# version3_PNP.net
KiCad netlist of a schematic drawn in EAGLE
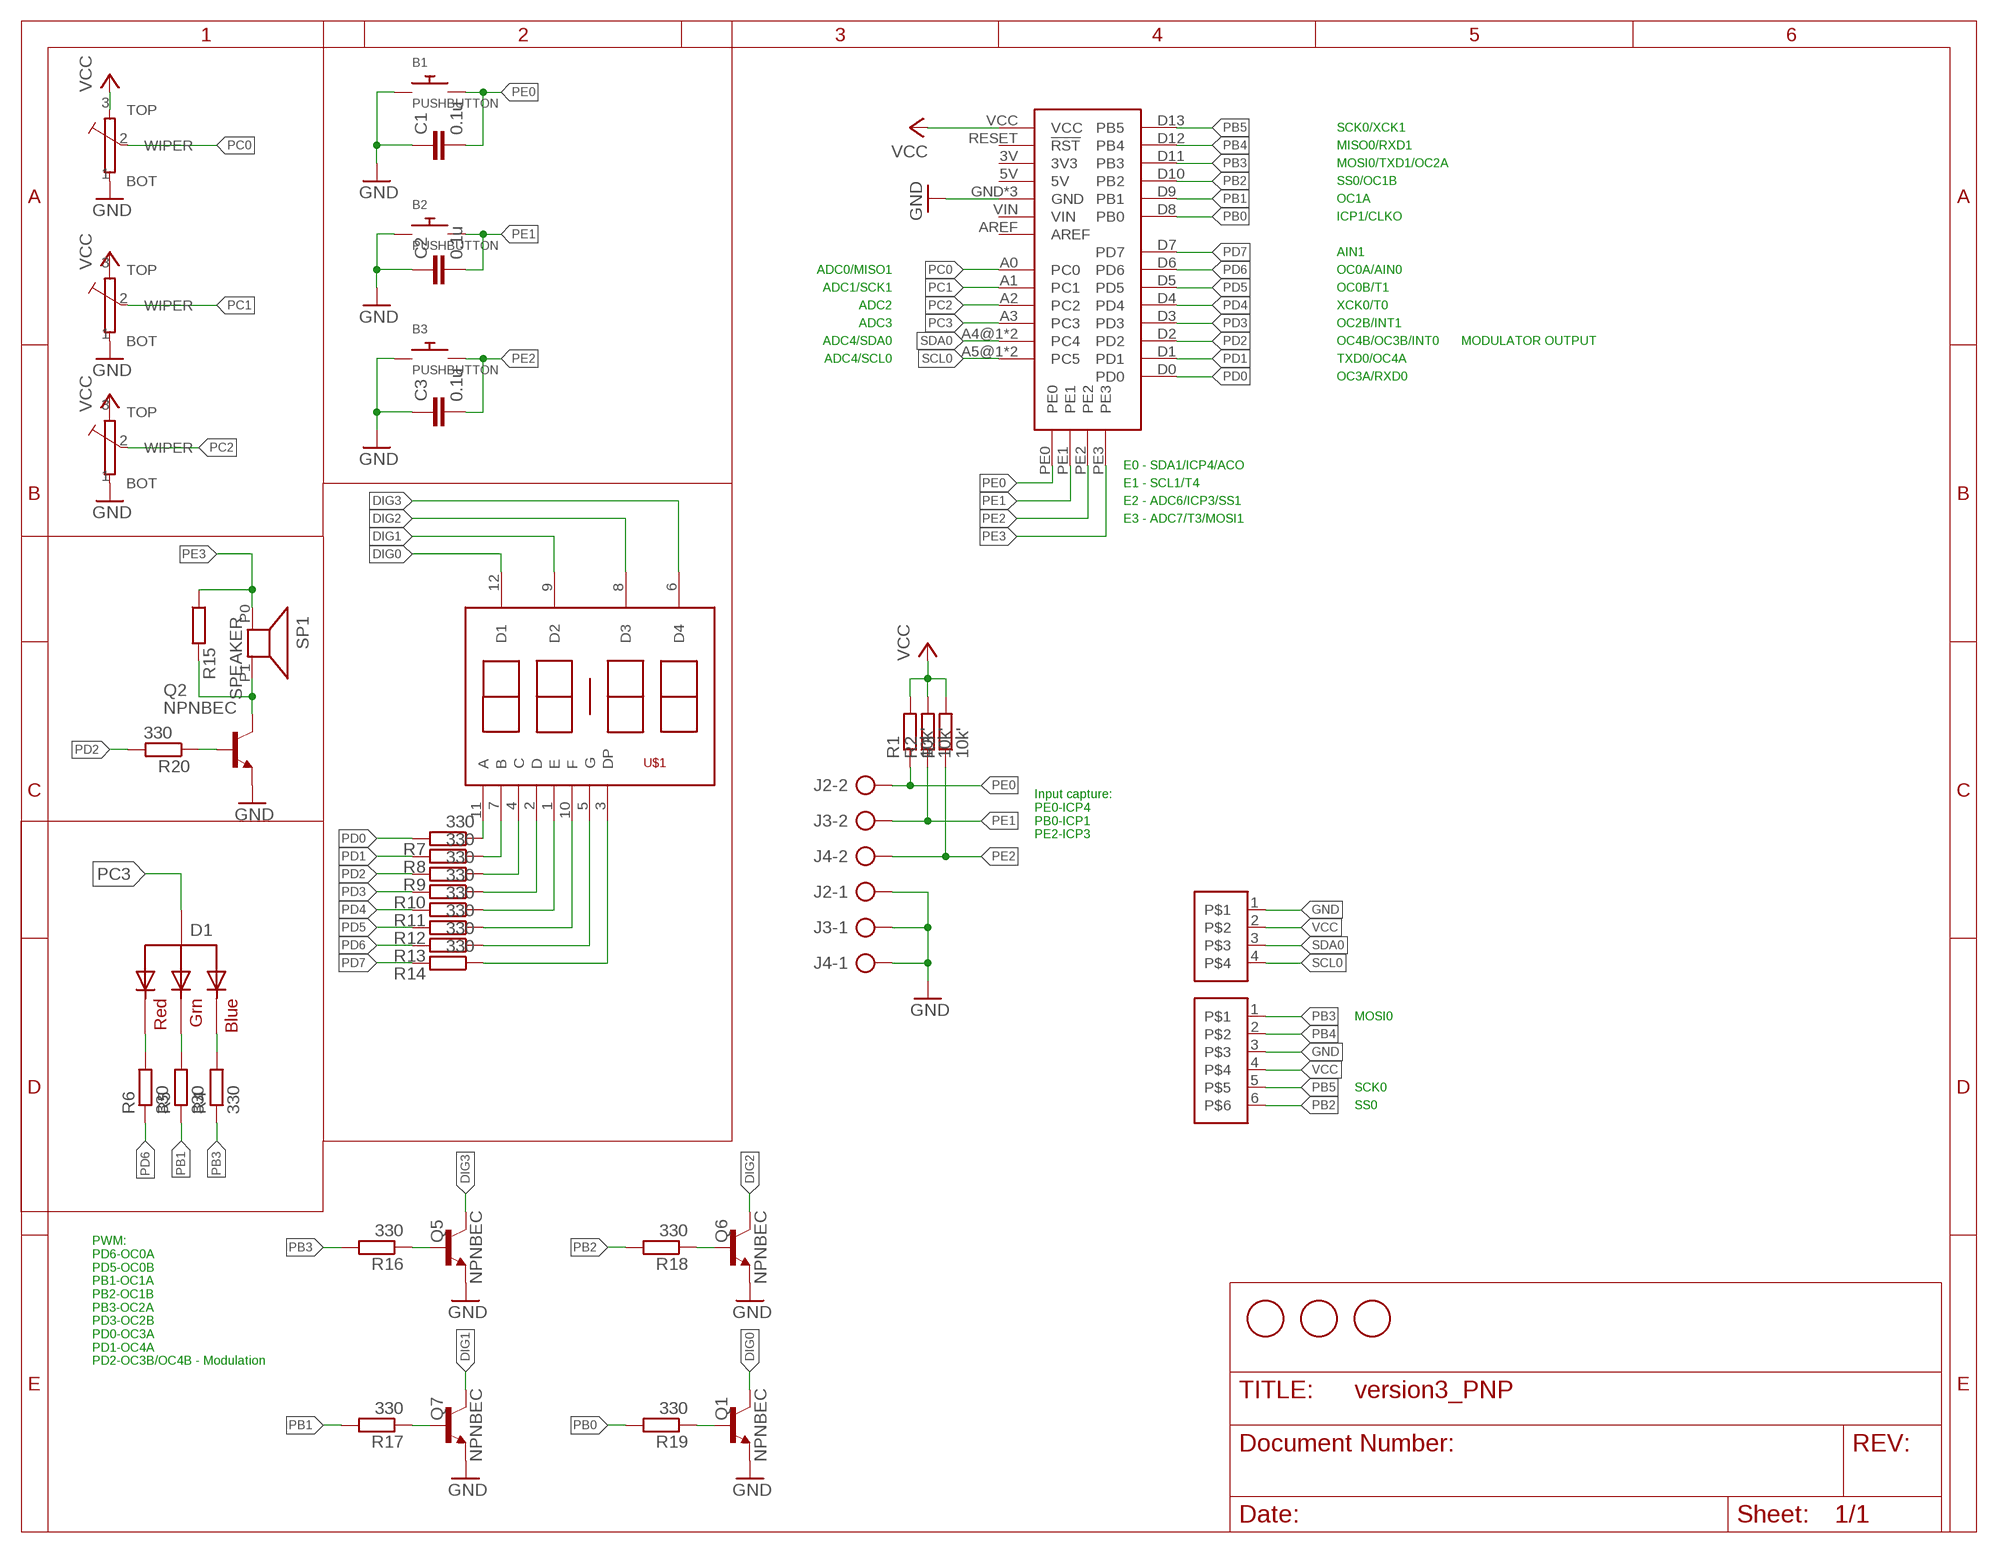
[diagram p0: schematic, sheet 1]

(export (version "E")
  (design (tool "Eeschema 10.0.6"))
  (components
    (comp (ref "AFID1")
      (value "FIDUCIAL")
      (footprint "eagle-import:FIDUCIAL_1MM")
      (libsource (lib "eagle-import") (part "FIDUCIAL"))
    )
    (comp (ref "AFID2")
      (value "FIDUCIAL")
      (footprint "eagle-import:FIDUCIAL_1MM")
      (libsource (lib "eagle-import") (part "FIDUCIAL"))
    )
    (comp (ref "AFID3")
      (value "FIDUCIAL")
      (footprint "eagle-import:FIDUCIAL_1MM")
      (libsource (lib "eagle-import") (part "FIDUCIAL"))
    )
    (comp (ref "B1")
      (value "PUSHBUTTON")
      (footprint "eagle-import:BUTTON_EVPBF")
      (libsource (lib "eagle-import") (part "PUSHBUTTON"))
    )
    (comp (ref "B2")
      (value "PUSHBUTTON")
      (footprint "eagle-import:BUTTON_EVPBF")
      (libsource (lib "eagle-import") (part "PUSHBUTTON"))
    )
    (comp (ref "B3")
      (value "PUSHBUTTON")
      (footprint "eagle-import:BUTTON_EVPBF")
      (libsource (lib "eagle-import") (part "PUSHBUTTON"))
    )
    (comp (ref "C1")
      (value "0.1u")
      (footprint "eagle-import:C0805")
      (libsource (lib "eagle-import") (part "C-EUC0805"))
    )
    (comp (ref "C2")
      (value "0.1u")
      (footprint "eagle-import:C0805")
      (libsource (lib "eagle-import") (part "C-EUC0805"))
    )
    (comp (ref "C3")
      (value "0.1u")
      (footprint "eagle-import:C0805")
      (libsource (lib "eagle-import") (part "C-EUC0805"))
    )
    (comp (ref "D1")
      (value "RGB_CA")
      (footprint "eagle-import:PLCC-4")
      (libsource (lib "eagle-import") (part "RGB_CA"))
    )
    (comp (ref "J1")
      (value "M04F")
      (footprint "eagle-import:1X04_FEMALE")
      (libsource (lib "eagle-import") (part "M04F"))
    )
    (comp (ref "J2")
      (value "1X02CLEAN")
      (footprint "eagle-import:1X02_CLEAN")
      (libsource (lib "eagle-import") (part "1X02CLEAN"))
    )
    (comp (ref "J3")
      (value "1X02CLEAN")
      (footprint "eagle-import:1X02_CLEAN")
      (libsource (lib "eagle-import") (part "1X02CLEAN"))
    )
    (comp (ref "J4")
      (value "1X02CLEAN")
      (footprint "eagle-import:1X02_CLEAN")
      (libsource (lib "eagle-import") (part "1X02CLEAN"))
    )
    (comp (ref "Q1")
      (value "NPNBEC")
      (footprint "eagle-import:SOT23")
      (libsource (lib "eagle-import") (part "NPNBEC"))
    )
    (comp (ref "Q2")
      (value "NPNBEC")
      (footprint "eagle-import:SOT23")
      (libsource (lib "eagle-import") (part "NPNBEC"))
    )
    (comp (ref "Q5")
      (value "NPNBEC")
      (footprint "eagle-import:SOT23")
      (libsource (lib "eagle-import") (part "NPNBEC"))
    )
    (comp (ref "Q6")
      (value "NPNBEC")
      (footprint "eagle-import:SOT23")
      (libsource (lib "eagle-import") (part "NPNBEC"))
    )
    (comp (ref "Q7")
      (value "NPNBEC")
      (footprint "eagle-import:SOT23")
      (libsource (lib "eagle-import") (part "NPNBEC"))
    )
    (comp (ref "R1")
      (value "10k'")
      (footprint "eagle-import:R0805")
      (libsource (lib "eagle-import") (part "R-EU_R0805"))
    )
    (comp (ref "R2")
      (value "10k'")
      (footprint "eagle-import:R0805")
      (libsource (lib "eagle-import") (part "R-EU_R0805"))
    )
    (comp (ref "R3")
      (value "10k'")
      (footprint "eagle-import:R0805")
      (libsource (lib "eagle-import") (part "R-EU_R0805"))
    )
    (comp (ref "R4")
      (value "330")
      (footprint "eagle-import:R0805")
      (libsource (lib "eagle-import") (part "R-EU_R0805"))
    )
    (comp (ref "R5")
      (value "330")
      (footprint "eagle-import:R0805")
      (libsource (lib "eagle-import") (part "R-EU_R0805"))
    )
    (comp (ref "R6")
      (value "330")
      (footprint "eagle-import:R0805")
      (libsource (lib "eagle-import") (part "R-EU_R0805"))
    )
    (comp (ref "R7")
      (value "330")
      (footprint "eagle-import:R0805")
      (libsource (lib "eagle-import") (part "R-EU_R0805"))
    )
    (comp (ref "R8")
      (value "330")
      (footprint "eagle-import:R0805")
      (libsource (lib "eagle-import") (part "R-EU_R0805"))
    )
    (comp (ref "R9")
      (value "330")
      (footprint "eagle-import:R0805")
      (libsource (lib "eagle-import") (part "R-EU_R0805"))
    )
    (comp (ref "R10")
      (value "330")
      (footprint "eagle-import:R0805")
      (libsource (lib "eagle-import") (part "R-EU_R0805"))
    )
    (comp (ref "R11")
      (value "330")
      (footprint "eagle-import:R0805")
      (libsource (lib "eagle-import") (part "R-EU_R0805"))
    )
    (comp (ref "R12")
      (value "330")
      (footprint "eagle-import:R0805")
      (libsource (lib "eagle-import") (part "R-EU_R0805"))
    )
    (comp (ref "R13")
      (value "330")
      (footprint "eagle-import:R0805")
      (libsource (lib "eagle-import") (part "R-EU_R0805"))
    )
    (comp (ref "R14")
      (value "330")
      (footprint "eagle-import:R0805")
      (libsource (lib "eagle-import") (part "R-EU_R0805"))
    )
    (comp (ref "R15")
      (value "R-EU_R0805")
      (footprint "eagle-import:R0805")
      (libsource (lib "eagle-import") (part "R-EU_R0805"))
    )
    (comp (ref "R16")
      (value "330")
      (footprint "eagle-import:R0805")
      (libsource (lib "eagle-import") (part "R-EU_R0805"))
    )
    (comp (ref "R17")
      (value "330")
      (footprint "eagle-import:R0805")
      (libsource (lib "eagle-import") (part "R-EU_R0805"))
    )
    (comp (ref "R18")
      (value "330")
      (footprint "eagle-import:R0805")
      (libsource (lib "eagle-import") (part "R-EU_R0805"))
    )
    (comp (ref "R19")
      (value "330")
      (footprint "eagle-import:R0805")
      (libsource (lib "eagle-import") (part "R-EU_R0805"))
    )
    (comp (ref "R20")
      (value "330")
      (footprint "eagle-import:R0805")
      (libsource (lib "eagle-import") (part "R-EU_R0805"))
    )
    (comp (ref "SP1")
      (value "SPEAKER")
      (footprint "eagle-import:PKMCS_SPEAKER")
      (libsource (lib "eagle-import") (part "SPEAKER"))
    )
    (comp (ref "TR1")
      (value "TRIMMTHUMB")
      (footprint "eagle-import:RV09")
      (libsource (lib "eagle-import") (part "TRIMMTHUMB"))
    )
    (comp (ref "TR2")
      (value "TRIMMTHUMB")
      (footprint "eagle-import:RV09")
      (libsource (lib "eagle-import") (part "TRIMMTHUMB"))
    )
    (comp (ref "TR3")
      (value "TRIMMTHUMB")
      (footprint "eagle-import:RV09")
      (libsource (lib "eagle-import") (part "TRIMMTHUMB"))
    )
    (comp (ref "U$1")
      (value "4DIG_7SEG_CATHODE")
      (footprint "eagle-import:4DIG_7SEG_CLOCK")
      (libsource (lib "eagle-import") (part "4DIG_7SEG_CATHODE"))
    )
    (comp (ref "U$2")
      (value "M06F")
      (footprint "eagle-import:1X06_FEMALE")
      (libsource (lib "eagle-import") (part "M06F"))
    )
    (comp (ref "U2")
      (value "XPLAINEDMINI328PB")
      (footprint "eagle-import:XPLAINEDMINI328P")
      (libsource (lib "eagle-import") (part "XPLAINEDMINI328PB"))
    )
  )
  (nets
    (net (code "1") (name "DIG0") (class "Default")
      (node (ref "Q1") (pin "3") (pinfunction "C_3") (pintype "passive"))
      (node (ref "U$1") (pin "12") (pinfunction "D1_12") (pintype "bidirectional"))
    )
    (net (code "2") (name "DIG1") (class "Default")
      (node (ref "Q7") (pin "3") (pinfunction "C_3") (pintype "passive"))
      (node (ref "U$1") (pin "9") (pinfunction "D2_9") (pintype "bidirectional"))
    )
    (net (code "3") (name "DIG2") (class "Default")
      (node (ref "Q6") (pin "3") (pinfunction "C_3") (pintype "passive"))
      (node (ref "U$1") (pin "8") (pinfunction "D3_8") (pintype "bidirectional"))
    )
    (net (code "4") (name "DIG3") (class "Default")
      (node (ref "Q5") (pin "3") (pinfunction "C_3") (pintype "passive"))
      (node (ref "U$1") (pin "6") (pinfunction "D4_6") (pintype "bidirectional"))
    )
    (net (code "5") (name "GND") (class "Default")
      (node (ref "B1") (pin "A1") (pinfunction "P$1_A1") (pintype "passive"))
      (node (ref "B1") (pin "A2") (pinfunction "P$1_A2") (pintype "passive"))
      (node (ref "B2") (pin "A1") (pinfunction "P$1_A1") (pintype "passive"))
      (node (ref "B2") (pin "A2") (pinfunction "P$1_A2") (pintype "passive"))
      (node (ref "B3") (pin "A1") (pinfunction "P$1_A1") (pintype "passive"))
      (node (ref "B3") (pin "A2") (pinfunction "P$1_A2") (pintype "passive"))
      (node (ref "C1") (pin "1") (pinfunction "1_1") (pintype "passive"))
      (node (ref "C2") (pin "1") (pinfunction "1_1") (pintype "passive"))
      (node (ref "C3") (pin "1") (pinfunction "1_1") (pintype "passive"))
      (node (ref "J1") (pin "1") (pinfunction "P$1_1") (pintype "bidirectional"))
      (node (ref "J2") (pin "1") (pinfunction "KL_1") (pintype "passive"))
      (node (ref "J3") (pin "1") (pinfunction "KL_1") (pintype "passive"))
      (node (ref "J4") (pin "1") (pinfunction "KL_1") (pintype "passive"))
      (node (ref "Q1") (pin "2") (pinfunction "E_2") (pintype "passive"))
      (node (ref "Q2") (pin "2") (pinfunction "E_2") (pintype "passive"))
      (node (ref "Q5") (pin "2") (pinfunction "E_2") (pintype "passive"))
      (node (ref "Q6") (pin "2") (pinfunction "E_2") (pintype "passive"))
      (node (ref "Q7") (pin "2") (pinfunction "E_2") (pintype "passive"))
      (node (ref "TR1") (pin "1") (pinfunction "BOT_1") (pintype "bidirectional"))
      (node (ref "TR2") (pin "1") (pinfunction "BOT_1") (pintype "bidirectional"))
      (node (ref "TR3") (pin "1") (pinfunction "BOT_1") (pintype "bidirectional"))
      (node (ref "U$2") (pin "3") (pinfunction "P$3_3") (pintype "bidirectional"))
      (node (ref "U2") (pin "GND") (pinfunction "GND_GND") (pintype "bidirectional"))
      (node (ref "U2") (pin "GND1") (pinfunction "GND_GND1") (pintype "bidirectional"))
      (node (ref "U2") (pin "GND2") (pinfunction "GND_GND2") (pintype "bidirectional"))
    )
    (net (code "6") (name "Net-(D1-BLUE)") (class "Default")
      (node (ref "D1") (pin "P2") (pinfunction "BLUE_P2") (pintype "bidirectional"))
      (node (ref "R4") (pin "2") (pinfunction "2_2") (pintype "passive"))
    )
    (net (code "7") (name "Net-(D1-GREEN)") (class "Default")
      (node (ref "D1") (pin "P3") (pinfunction "GREEN_P3") (pintype "bidirectional"))
      (node (ref "R5") (pin "2") (pinfunction "2_2") (pintype "passive"))
    )
    (net (code "8") (name "Net-(D1-RED)") (class "Default")
      (node (ref "D1") (pin "P4") (pinfunction "RED_P4") (pintype "bidirectional"))
      (node (ref "R6") (pin "2") (pinfunction "2_2") (pintype "passive"))
    )
    (net (code "9") (name "Net-(Q1-B)") (class "Default")
      (node (ref "Q1") (pin "1") (pinfunction "B_1") (pintype "passive"))
      (node (ref "R19") (pin "1") (pinfunction "1_1") (pintype "passive"))
    )
    (net (code "10") (name "Net-(Q2-B)") (class "Default")
      (node (ref "Q2") (pin "1") (pinfunction "B_1") (pintype "passive"))
      (node (ref "R20") (pin "1") (pinfunction "1_1") (pintype "passive"))
    )
    (net (code "11") (name "Net-(Q2-C)") (class "Default")
      (node (ref "Q2") (pin "3") (pinfunction "C_3") (pintype "passive"))
      (node (ref "R15") (pin "2") (pinfunction "2_2") (pintype "passive"))
      (node (ref "SP1") (pin "P1") (pinfunction "2_P1") (pintype "passive"))
    )
    (net (code "12") (name "Net-(Q5-B)") (class "Default")
      (node (ref "Q5") (pin "1") (pinfunction "B_1") (pintype "passive"))
      (node (ref "R16") (pin "1") (pinfunction "1_1") (pintype "passive"))
    )
    (net (code "13") (name "Net-(Q6-B)") (class "Default")
      (node (ref "Q6") (pin "1") (pinfunction "B_1") (pintype "passive"))
      (node (ref "R18") (pin "1") (pinfunction "1_1") (pintype "passive"))
    )
    (net (code "14") (name "Net-(Q7-B)") (class "Default")
      (node (ref "Q7") (pin "1") (pinfunction "B_1") (pintype "passive"))
      (node (ref "R17") (pin "1") (pinfunction "1_1") (pintype "passive"))
    )
    (net (code "15") (name "Net-(U$1-A)") (class "Default")
      (node (ref "R7") (pin "1") (pinfunction "1_1") (pintype "passive"))
      (node (ref "U$1") (pin "11") (pinfunction "A_11") (pintype "bidirectional"))
    )
    (net (code "16") (name "Net-(U$1-B)") (class "Default")
      (node (ref "R8") (pin "1") (pinfunction "1_1") (pintype "passive"))
      (node (ref "U$1") (pin "7") (pinfunction "B_7") (pintype "bidirectional"))
    )
    (net (code "17") (name "Net-(U$1-C)") (class "Default")
      (node (ref "R9") (pin "1") (pinfunction "1_1") (pintype "passive"))
      (node (ref "U$1") (pin "4") (pinfunction "C_4") (pintype "bidirectional"))
    )
    (net (code "18") (name "Net-(U$1-D)") (class "Default")
      (node (ref "R10") (pin "1") (pinfunction "1_1") (pintype "passive"))
      (node (ref "U$1") (pin "2") (pinfunction "D_2") (pintype "bidirectional"))
    )
    (net (code "19") (name "Net-(U$1-DP)") (class "Default")
      (node (ref "R14") (pin "1") (pinfunction "1_1") (pintype "passive"))
      (node (ref "U$1") (pin "3") (pinfunction "DP_3") (pintype "bidirectional"))
    )
    (net (code "20") (name "Net-(U$1-E)") (class "Default")
      (node (ref "R11") (pin "1") (pinfunction "1_1") (pintype "passive"))
      (node (ref "U$1") (pin "1") (pinfunction "E_1") (pintype "bidirectional"))
    )
    (net (code "21") (name "Net-(U$1-F)") (class "Default")
      (node (ref "R12") (pin "1") (pinfunction "1_1") (pintype "passive"))
      (node (ref "U$1") (pin "10") (pinfunction "F_10") (pintype "bidirectional"))
    )
    (net (code "22") (name "Net-(U$1-G)") (class "Default")
      (node (ref "R13") (pin "1") (pinfunction "1_1") (pintype "passive"))
      (node (ref "U$1") (pin "5") (pinfunction "G_5") (pintype "bidirectional"))
    )
    (net (code "23") (name "PB0") (class "Default")
      (node (ref "R19") (pin "2") (pinfunction "2_2") (pintype "passive"))
      (node (ref "U2") (pin "D8") (pinfunction "PB0_D8") (pintype "bidirectional"))
    )
    (net (code "24") (name "PB1") (class "Default")
      (node (ref "R17") (pin "2") (pinfunction "2_2") (pintype "passive"))
      (node (ref "R5") (pin "1") (pinfunction "1_1") (pintype "passive"))
      (node (ref "U2") (pin "D9") (pinfunction "PB1_D9") (pintype "bidirectional"))
    )
    (net (code "25") (name "PB2") (class "Default")
      (node (ref "R18") (pin "2") (pinfunction "2_2") (pintype "passive"))
      (node (ref "U$2") (pin "6") (pinfunction "P$6_6") (pintype "bidirectional"))
      (node (ref "U2") (pin "D10") (pinfunction "PB2_D10") (pintype "bidirectional"))
    )
    (net (code "26") (name "PB3") (class "Default")
      (node (ref "R16") (pin "2") (pinfunction "2_2") (pintype "passive"))
      (node (ref "R4") (pin "1") (pinfunction "1_1") (pintype "passive"))
      (node (ref "U$2") (pin "1") (pinfunction "P$1_1") (pintype "bidirectional"))
      (node (ref "U2") (pin "D11") (pinfunction "PB3_D11") (pintype "bidirectional"))
    )
    (net (code "27") (name "PB4") (class "Default")
      (node (ref "U$2") (pin "2") (pinfunction "P$2_2") (pintype "bidirectional"))
      (node (ref "U2") (pin "D12") (pinfunction "PB4_D12") (pintype "bidirectional"))
    )
    (net (code "28") (name "PB5") (class "Default")
      (node (ref "U$2") (pin "5") (pinfunction "P$5_5") (pintype "bidirectional"))
      (node (ref "U2") (pin "D13") (pinfunction "PB5_D13") (pintype "bidirectional"))
    )
    (net (code "29") (name "PC0") (class "Default")
      (node (ref "TR1") (pin "2") (pinfunction "WIPER_2") (pintype "bidirectional"))
      (node (ref "U2") (pin "A0") (pinfunction "PC0_A0") (pintype "bidirectional"))
    )
    (net (code "30") (name "PC1") (class "Default")
      (node (ref "TR2") (pin "2") (pinfunction "WIPER_2") (pintype "bidirectional"))
      (node (ref "U2") (pin "A1") (pinfunction "PC1_A1") (pintype "bidirectional"))
    )
    (net (code "31") (name "PC2") (class "Default")
      (node (ref "TR3") (pin "2") (pinfunction "WIPER_2") (pintype "bidirectional"))
      (node (ref "U2") (pin "A2") (pinfunction "PC2_A2") (pintype "bidirectional"))
    )
    (net (code "32") (name "PC3") (class "Default")
      (node (ref "D1") (pin "P1") (pinfunction "VCC_P1") (pintype "bidirectional"))
      (node (ref "U2") (pin "A3") (pinfunction "PC3_A3") (pintype "bidirectional"))
    )
    (net (code "33") (name "PD0") (class "Default")
      (node (ref "R7") (pin "2") (pinfunction "2_2") (pintype "passive"))
      (node (ref "U2") (pin "D0") (pinfunction "PD0_D0") (pintype "bidirectional"))
    )
    (net (code "34") (name "PD1") (class "Default")
      (node (ref "R8") (pin "2") (pinfunction "2_2") (pintype "passive"))
      (node (ref "U2") (pin "D1") (pinfunction "PD1_D1") (pintype "bidirectional"))
    )
    (net (code "35") (name "PD2") (class "Default")
      (node (ref "R20") (pin "2") (pinfunction "2_2") (pintype "passive"))
      (node (ref "R9") (pin "2") (pinfunction "2_2") (pintype "passive"))
      (node (ref "U2") (pin "D2") (pinfunction "PD2_D2") (pintype "bidirectional"))
    )
    (net (code "36") (name "PD3") (class "Default")
      (node (ref "R10") (pin "2") (pinfunction "2_2") (pintype "passive"))
      (node (ref "U2") (pin "D3") (pinfunction "PD3_D3") (pintype "bidirectional"))
    )
    (net (code "37") (name "PD4") (class "Default")
      (node (ref "R11") (pin "2") (pinfunction "2_2") (pintype "passive"))
      (node (ref "U2") (pin "D4") (pinfunction "PD4_D4") (pintype "bidirectional"))
    )
    (net (code "38") (name "PD5") (class "Default")
      (node (ref "R12") (pin "2") (pinfunction "2_2") (pintype "passive"))
      (node (ref "U2") (pin "D5") (pinfunction "PD5_D5") (pintype "bidirectional"))
    )
    (net (code "39") (name "PD6") (class "Default")
      (node (ref "R13") (pin "2") (pinfunction "2_2") (pintype "passive"))
      (node (ref "R6") (pin "1") (pinfunction "1_1") (pintype "passive"))
      (node (ref "U2") (pin "D6") (pinfunction "PD6_D6") (pintype "bidirectional"))
    )
    (net (code "40") (name "PD7") (class "Default")
      (node (ref "R14") (pin "2") (pinfunction "2_2") (pintype "passive"))
      (node (ref "U2") (pin "D7") (pinfunction "PD7_D7") (pintype "bidirectional"))
    )
    (net (code "41") (name "PE0") (class "Default")
      (node (ref "B1") (pin "B1") (pinfunction "P$2_B1") (pintype "passive"))
      (node (ref "B1") (pin "B2") (pinfunction "P$2_B2") (pintype "passive"))
      (node (ref "C1") (pin "2") (pinfunction "2_2") (pintype "passive"))
      (node (ref "J2") (pin "2") (pinfunction "KL_2") (pintype "passive"))
      (node (ref "R1") (pin "1") (pinfunction "1_1") (pintype "passive"))
      (node (ref "U2") (pin "PE0") (pinfunction "PE0_PE0") (pintype "bidirectional"))
    )
    (net (code "42") (name "PE1") (class "Default")
      (node (ref "B2") (pin "B1") (pinfunction "P$2_B1") (pintype "passive"))
      (node (ref "B2") (pin "B2") (pinfunction "P$2_B2") (pintype "passive"))
      (node (ref "C2") (pin "2") (pinfunction "2_2") (pintype "passive"))
      (node (ref "J3") (pin "2") (pinfunction "KL_2") (pintype "passive"))
      (node (ref "R2") (pin "1") (pinfunction "1_1") (pintype "passive"))
      (node (ref "U2") (pin "PE1") (pinfunction "PE1_PE1") (pintype "bidirectional"))
    )
    (net (code "43") (name "PE2") (class "Default")
      (node (ref "B3") (pin "B1") (pinfunction "P$2_B1") (pintype "passive"))
      (node (ref "B3") (pin "B2") (pinfunction "P$2_B2") (pintype "passive"))
      (node (ref "C3") (pin "2") (pinfunction "2_2") (pintype "passive"))
      (node (ref "J4") (pin "2") (pinfunction "KL_2") (pintype "passive"))
      (node (ref "R3") (pin "1") (pinfunction "1_1") (pintype "passive"))
      (node (ref "U2") (pin "PE2") (pinfunction "PE2_PE2") (pintype "bidirectional"))
    )
    (net (code "44") (name "PE3") (class "Default")
      (node (ref "R15") (pin "1") (pinfunction "1_1") (pintype "passive"))
      (node (ref "SP1") (pin "P0") (pinfunction "1_P0") (pintype "passive"))
      (node (ref "U2") (pin "PE3") (pinfunction "PE3_PE3") (pintype "bidirectional"))
    )
    (net (code "45") (name "SCL0") (class "Default")
      (node (ref "J1") (pin "4") (pinfunction "P$4_4") (pintype "bidirectional"))
      (node (ref "U2") (pin "A5@1") (pinfunction "PC5_A5@1") (pintype "bidirectional"))
      (node (ref "U2") (pin "A5@2") (pinfunction "PC5_A5@2") (pintype "bidirectional"))
    )
    (net (code "46") (name "SDA0") (class "Default")
      (node (ref "J1") (pin "3") (pinfunction "P$3_3") (pintype "bidirectional"))
      (node (ref "U2") (pin "A4@1") (pinfunction "PC4_A4@1") (pintype "bidirectional"))
      (node (ref "U2") (pin "A4@2") (pinfunction "PC4_A4@2") (pintype "bidirectional"))
    )
    (net (code "47") (name "VCC") (class "Default")
      (node (ref "J1") (pin "2") (pinfunction "P$2_2") (pintype "bidirectional"))
      (node (ref "R1") (pin "2") (pinfunction "2_2") (pintype "passive"))
      (node (ref "R2") (pin "2") (pinfunction "2_2") (pintype "passive"))
      (node (ref "R3") (pin "2") (pinfunction "2_2") (pintype "passive"))
      (node (ref "TR1") (pin "3") (pinfunction "TOP_3") (pintype "bidirectional"))
      (node (ref "TR2") (pin "3") (pinfunction "TOP_3") (pintype "bidirectional"))
      (node (ref "TR3") (pin "3") (pinfunction "TOP_3") (pintype "bidirectional"))
      (node (ref "U$2") (pin "4") (pinfunction "P$4_4") (pintype "bidirectional"))
      (node (ref "U2") (pin "VCC") (pinfunction "VCC_VCC") (pintype "bidirectional"))
    )
    (net (code "48") (name "unconnected-(U2-3V3-Pad3V)") (class "Default")
      (node (ref "U2") (pin "3V") (pinfunction "3V3_3V") (pintype "bidirectional"))
    )
    (net (code "49") (name "unconnected-(U2-Pad5V)") (class "Default")
      (node (ref "U2") (pin "5V") (pinfunction "5V_5V") (pintype "bidirectional"))
    )
    (net (code "50") (name "unconnected-(U2-PadAREF)") (class "Default")
      (node (ref "U2") (pin "AREF") (pinfunction "AREF_AREF") (pintype "bidirectional"))
    )
    (net (code "51") (name "unconnected-(U2-PadVIN)") (class "Default")
      (node (ref "U2") (pin "VIN") (pinfunction "VIN_VIN") (pintype "bidirectional"))
    )
    (net (code "52") (name "unconnected-(U2-~{RST}-PadRESET)") (class "Default")
      (node (ref "U2") (pin "RESET") (pinfunction "~{RST}_RESET") (pintype "bidirectional"))
    )
  )
)
